# Sheet1.net
KiCad netlist of a schematic drawn in Altium Designer
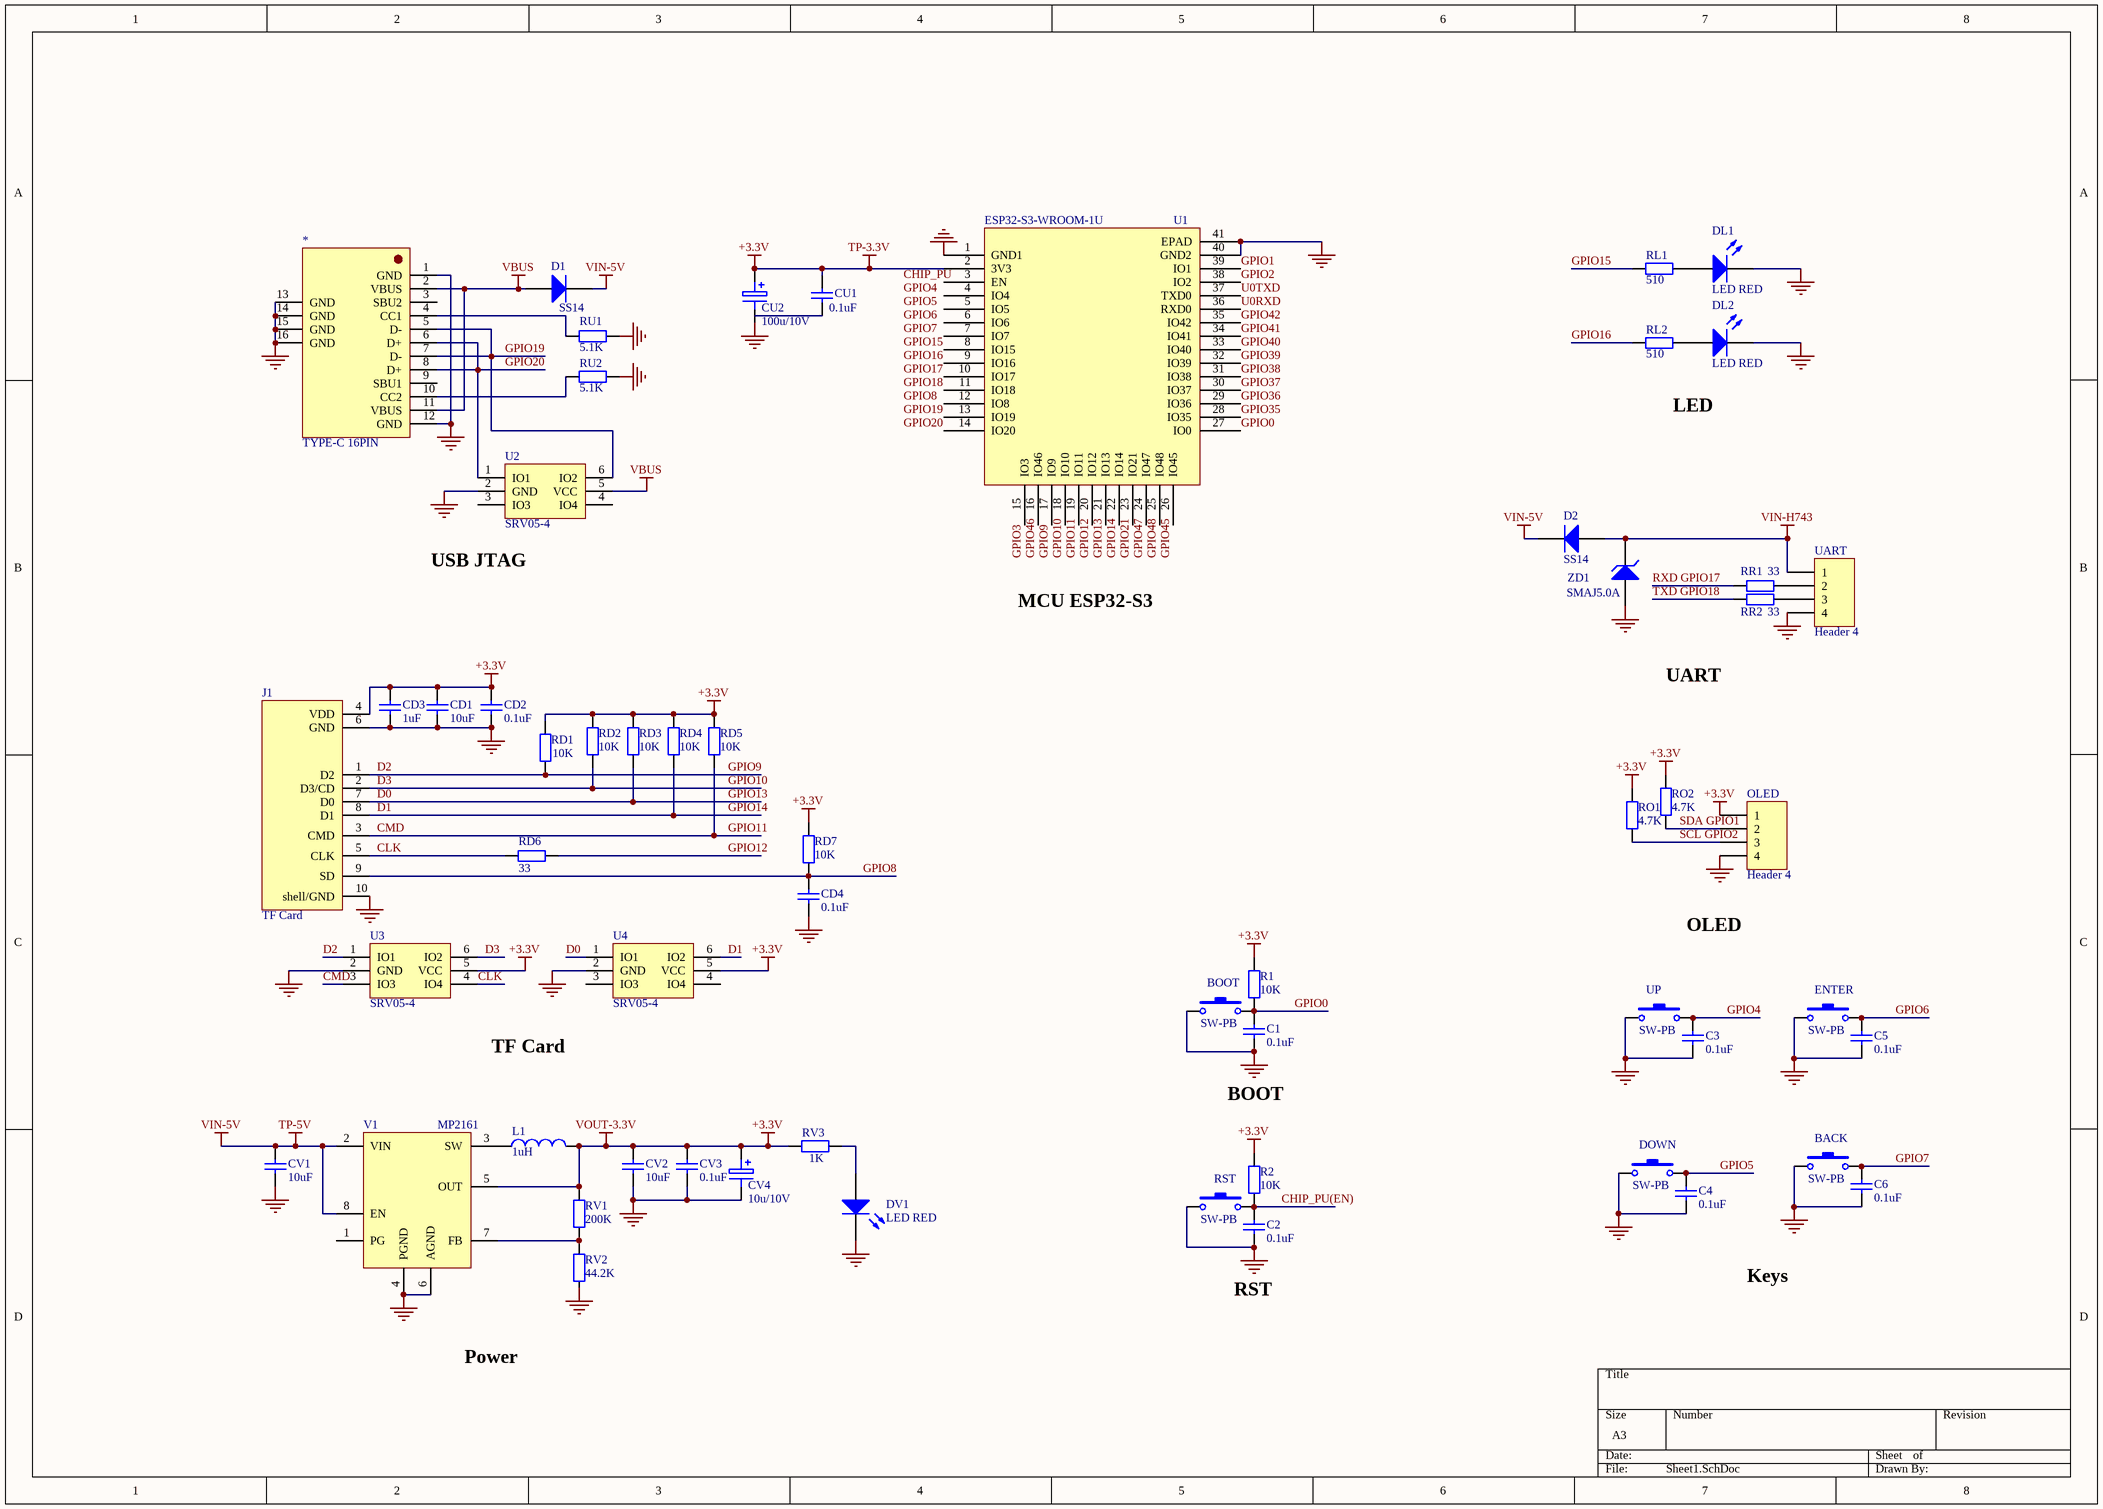
[diagram p0: Sheet1.SchDoc]

(export (version "E")
  (design (tool "Eeschema 10.0.6"))
  (components
    (comp (ref "*") (value "TYPE-C 16PIN") (libsource (lib "Schlib1") (part "TYPE-C 16PIN")))
    (comp (ref "BACK")
      (value "SW-PB")
      (footprint "SPST-2")
      (description "Switch")
      (fields (field (name "PUBLISHER") "Altium Limited"))
      (libsource (lib "Miscellaneous Devices") (part "SW-PB"))
    )
    (comp (ref "BOOT")
      (value "SW-PB")
      (footprint "SPST-2")
      (description "Switch")
      (fields (field (name "PUBLISHER") "Altium Limited"))
      (libsource (lib "Miscellaneous Devices") (part "SW-PB"))
    )
    (comp (ref "C1")
      (value "0.1uF")
      (footprint "RAD-0.3")
      (description "Capacitor")
      (fields (field (name "Comment") "Cap") (field (name "PUBLISHER") "Altium Limited"))
      (libsource (lib "Miscellaneous Devices") (part "Cap"))
    )
    (comp (ref "C2")
      (value "0.1uF")
      (footprint "RAD-0.3")
      (description "Capacitor")
      (fields (field (name "Comment") "Cap") (field (name "PUBLISHER") "Altium Limited"))
      (libsource (lib "Miscellaneous Devices") (part "Cap"))
    )
    (comp (ref "C3")
      (value "0.1uF")
      (footprint "RAD-0.3")
      (description "Capacitor")
      (fields (field (name "Comment") "Cap") (field (name "PUBLISHER") "Altium Limited"))
      (libsource (lib "Miscellaneous Devices") (part "Cap"))
    )
    (comp (ref "C4")
      (value "0.1uF")
      (footprint "RAD-0.3")
      (description "Capacitor")
      (fields (field (name "Comment") "Cap") (field (name "PUBLISHER") "Altium Limited"))
      (libsource (lib "Miscellaneous Devices") (part "Cap"))
    )
    (comp (ref "C5")
      (value "0.1uF")
      (footprint "RAD-0.3")
      (description "Capacitor")
      (fields (field (name "Comment") "Cap") (field (name "PUBLISHER") "Altium Limited"))
      (libsource (lib "Miscellaneous Devices") (part "Cap"))
    )
    (comp (ref "C6")
      (value "0.1uF")
      (footprint "RAD-0.3")
      (description "Capacitor")
      (fields (field (name "Comment") "Cap") (field (name "PUBLISHER") "Altium Limited"))
      (libsource (lib "Miscellaneous Devices") (part "Cap"))
    )
    (comp (ref "CD1")
      (value "10uF")
      (footprint "RAD-0.3")
      (description "Capacitor")
      (fields (field (name "Comment") "Cap") (field (name "PUBLISHER") "Altium Limited"))
      (libsource (lib "Miscellaneous Devices") (part "Cap"))
    )
    (comp (ref "CD2")
      (value "0.1uF")
      (footprint "RAD-0.3")
      (description "Capacitor")
      (fields (field (name "Comment") "Cap") (field (name "PUBLISHER") "Altium Limited"))
      (libsource (lib "Miscellaneous Devices") (part "Cap"))
    )
    (comp (ref "CD3")
      (value "1uF")
      (footprint "RAD-0.3")
      (description "Capacitor")
      (fields (field (name "Comment") "Cap") (field (name "PUBLISHER") "Altium Limited"))
      (libsource (lib "Miscellaneous Devices") (part "Cap"))
    )
    (comp (ref "CD4")
      (value "0.1uF")
      (footprint "RAD-0.3")
      (description "Capacitor")
      (fields (field (name "Comment") "Cap") (field (name "PUBLISHER") "Altium Limited"))
      (libsource (lib "Miscellaneous Devices") (part "Cap"))
    )
    (comp (ref "CU1")
      (value "0.1uF")
      (footprint "RAD-0.3")
      (description "Capacitor")
      (fields (field (name "Comment") "Cap") (field (name "PUBLISHER") "Altium Limited"))
      (libsource (lib "Miscellaneous Devices") (part "Cap"))
    )
    (comp (ref "CU2")
      (value "100u/10V")
      (description "Electrolytic Capacitor")
      (libsource (lib "*") (part "ELECTRO1"))
    )
    (comp (ref "CV1")
      (value "10uF")
      (footprint "RAD-0.3")
      (description "Capacitor")
      (fields (field (name "Comment") "Cap") (field (name "PUBLISHER") "Altium Limited"))
      (libsource (lib "Miscellaneous Devices") (part "Cap"))
    )
    (comp (ref "CV2")
      (value "10uF")
      (footprint "RAD-0.3")
      (description "Capacitor")
      (fields (field (name "Comment") "Cap") (field (name "PUBLISHER") "Altium Limited"))
      (libsource (lib "Miscellaneous Devices") (part "Cap"))
    )
    (comp (ref "CV3")
      (value "0.1uF")
      (footprint "RAD-0.3")
      (description "Capacitor")
      (fields (field (name "Comment") "Cap") (field (name "PUBLISHER") "Altium Limited"))
      (libsource (lib "Miscellaneous Devices") (part "Cap"))
    )
    (comp (ref "CV4")
      (value "10u/10V")
      (description "Electrolytic Capacitor")
      (libsource (lib "*") (part "ELECTRO1"))
    )
    (comp (ref "D1")
      (value "SS14")
      (footprint "SMC")
      (description "Default Diode")
      (fields (field (name "PUBLISHER") "Altium Limited"))
      (libsource (lib "Miscellaneous Devices") (part "Diode"))
    )
    (comp (ref "D2")
      (value "SS14")
      (footprint "SMC")
      (description "Default Diode")
      (fields (field (name "PUBLISHER") "Altium Limited"))
      (libsource (lib "Miscellaneous Devices") (part "Diode"))
    )
    (comp (ref "DL1")
      (value "LED RED")
      (footprint "3.2X1.6X1.1")
      (description "Typical RED, GREEN, YELLOW, AMBER GaAs LED")
      (fields (field (name "PUBLISHER") "Altium Limited"))
      (libsource (lib "Miscellaneous Devices") (part "LED2"))
    )
    (comp (ref "DL2")
      (value "LED RED")
      (footprint "3.2X1.6X1.1")
      (description "Typical RED, GREEN, YELLOW, AMBER GaAs LED")
      (fields (field (name "PUBLISHER") "Altium Limited"))
      (libsource (lib "Miscellaneous Devices") (part "LED2"))
    )
    (comp (ref "DOWN")
      (value "SW-PB")
      (footprint "SPST-2")
      (description "Switch")
      (fields (field (name "PUBLISHER") "Altium Limited"))
      (libsource (lib "Miscellaneous Devices") (part "SW-PB"))
    )
    (comp (ref "DV1")
      (value "LED RED")
      (footprint "3.2X1.6X1.1")
      (description "Typical RED, GREEN, YELLOW, AMBER GaAs LED")
      (fields (field (name "PUBLISHER") "Altium Limited"))
      (libsource (lib "Miscellaneous Devices") (part "LED2"))
    )
    (comp (ref "ENTER")
      (value "SW-PB")
      (footprint "SPST-2")
      (description "Switch")
      (fields (field (name "PUBLISHER") "Altium Limited"))
      (libsource (lib "Miscellaneous Devices") (part "SW-PB"))
    )
    (comp (ref "ESP32-S3-WROOM-1U") (value "U1") (libsource (lib "Schlib1") (part "ESP32-S3-WROOM-1U")))
    (comp (ref "J1") (value "TF Card") (libsource (lib "Schlib1") (part "TF Card")))
    (comp (ref "L1")
      (value "1uH")
      (footprint "0402-A")
      (description "Inductor")
      (fields (field (name "PUBLISHER") "Altium Limited"))
      (libsource (lib "Miscellaneous Devices") (part "Inductor"))
    )
    (comp (ref "OLED")
      (value "Header 4")
      (footprint "HDR1X4")
      (description "Header, 4-Pin")
      (fields (field (name "PUBLISHER") "Altium Limited"))
      (libsource (lib "Miscellaneous Connectors") (part "Header 4"))
    )
    (comp (ref "R1")
      (value "10K")
      (footprint "AXIAL-0.4")
      (description "Resistor")
      (fields (field (name "Comment") "Res2") (field (name "PUBLISHER") "Altium Limited"))
      (libsource (lib "Miscellaneous Devices") (part "Res2"))
    )
    (comp (ref "R2")
      (value "10K")
      (footprint "AXIAL-0.4")
      (description "Resistor")
      (fields (field (name "Comment") "Res2") (field (name "PUBLISHER") "Altium Limited"))
      (libsource (lib "Miscellaneous Devices") (part "Res2"))
    )
    (comp (ref "RD1")
      (value "10K")
      (footprint "AXIAL-0.4")
      (description "Resistor")
      (fields (field (name "Comment") "Res2") (field (name "PUBLISHER") "Altium Limited"))
      (libsource (lib "Miscellaneous Devices") (part "Res2"))
    )
    (comp (ref "RD2")
      (value "10K")
      (footprint "AXIAL-0.4")
      (description "Resistor")
      (fields (field (name "Comment") "Res2") (field (name "PUBLISHER") "Altium Limited"))
      (libsource (lib "Miscellaneous Devices") (part "Res2"))
    )
    (comp (ref "RD3")
      (value "10K")
      (footprint "AXIAL-0.4")
      (description "Resistor")
      (fields (field (name "Comment") "Res2") (field (name "PUBLISHER") "Altium Limited"))
      (libsource (lib "Miscellaneous Devices") (part "Res2"))
    )
    (comp (ref "RD4")
      (value "10K")
      (footprint "AXIAL-0.4")
      (description "Resistor")
      (fields (field (name "Comment") "Res2") (field (name "PUBLISHER") "Altium Limited"))
      (libsource (lib "Miscellaneous Devices") (part "Res2"))
    )
    (comp (ref "RD5")
      (value "10K")
      (footprint "AXIAL-0.4")
      (description "Resistor")
      (fields (field (name "Comment") "Res2") (field (name "PUBLISHER") "Altium Limited"))
      (libsource (lib "Miscellaneous Devices") (part "Res2"))
    )
    (comp (ref "RD6")
      (value "33")
      (footprint "AXIAL-0.4")
      (description "Resistor")
      (fields (field (name "Comment") "Res2") (field (name "PUBLISHER") "Altium Limited"))
      (libsource (lib "") (part "Res2_1"))
    )
    (comp (ref "RD7")
      (value "10K")
      (footprint "AXIAL-0.4")
      (description "Resistor")
      (fields (field (name "Comment") "Res2") (field (name "PUBLISHER") "Altium Limited"))
      (libsource (lib "Miscellaneous Devices") (part "Res2"))
    )
    (comp (ref "RL1")
      (value "510")
      (footprint "AXIAL-0.4")
      (description "Resistor")
      (fields (field (name "PUBLISHER") "Altium Limited"))
      (libsource (lib "") (part "Res2_1"))
    )
    (comp (ref "RL2")
      (value "510")
      (footprint "AXIAL-0.4")
      (description "Resistor")
      (fields (field (name "PUBLISHER") "Altium Limited"))
      (libsource (lib "") (part "Res2_1"))
    )
    (comp (ref "RO1")
      (value "4.7K")
      (footprint "AXIAL-0.4")
      (description "Resistor")
      (fields (field (name "Comment") "Res2") (field (name "PUBLISHER") "Altium Limited"))
      (libsource (lib "Miscellaneous Devices") (part "Res2"))
    )
    (comp (ref "RO2")
      (value "4.7K")
      (footprint "AXIAL-0.4")
      (description "Resistor")
      (fields (field (name "Comment") "Res2") (field (name "PUBLISHER") "Altium Limited"))
      (libsource (lib "Miscellaneous Devices") (part "Res2"))
    )
    (comp (ref "RR1")
      (value "33")
      (footprint "AXIAL-0.4")
      (description "Resistor")
      (fields (field (name "Comment") "Res2") (field (name "PUBLISHER") "Altium Limited"))
      (libsource (lib "") (part "Res2_1"))
    )
    (comp (ref "RR2")
      (value "33")
      (footprint "AXIAL-0.4")
      (description "Resistor")
      (fields (field (name "Comment") "Res2") (field (name "PUBLISHER") "Altium Limited"))
      (libsource (lib "") (part "Res2_1"))
    )
    (comp (ref "RST")
      (value "SW-PB")
      (footprint "SPST-2")
      (description "Switch")
      (fields (field (name "PUBLISHER") "Altium Limited"))
      (libsource (lib "Miscellaneous Devices") (part "SW-PB"))
    )
    (comp (ref "RU1")
      (value "5.1K")
      (footprint "AXIAL-0.4")
      (description "Resistor")
      (fields (field (name "PUBLISHER") "Altium Limited"))
      (libsource (lib "") (part "Res2_1"))
    )
    (comp (ref "RU2")
      (value "5.1K")
      (footprint "AXIAL-0.4")
      (description "Resistor")
      (fields (field (name "PUBLISHER") "Altium Limited"))
      (libsource (lib "") (part "Res2_1"))
    )
    (comp (ref "RV1")
      (value "200K")
      (footprint "AXIAL-0.4")
      (description "Resistor")
      (fields (field (name "Comment") "Res2") (field (name "PUBLISHER") "Altium Limited"))
      (libsource (lib "Miscellaneous Devices") (part "Res2"))
    )
    (comp (ref "RV2")
      (value "44.2K")
      (footprint "AXIAL-0.4")
      (description "Resistor")
      (fields (field (name "Comment") "Res2") (field (name "PUBLISHER") "Altium Limited"))
      (libsource (lib "Miscellaneous Devices") (part "Res2"))
    )
    (comp (ref "RV3")
      (value "1K")
      (footprint "AXIAL-0.4")
      (description "Resistor")
      (fields (field (name "PUBLISHER") "Altium Limited"))
      (libsource (lib "") (part "Res2_1"))
    )
    (comp (ref "U2") (value "SRV05-4") (libsource (lib "Schlib1") (part "SRV05-4")))
    (comp (ref "U3") (value "SRV05-4") (libsource (lib "Schlib1") (part "SRV05-4")))
    (comp (ref "U4") (value "SRV05-4") (libsource (lib "Schlib1") (part "SRV05-4")))
    (comp (ref "UART")
      (value "Header 4")
      (footprint "HDR1X4")
      (description "Header, 4-Pin")
      (fields (field (name "PUBLISHER") "Altium Limited"))
      (libsource (lib "Miscellaneous Connectors") (part "Header 4"))
    )
    (comp (ref "UP")
      (value "SW-PB")
      (footprint "SPST-2")
      (description "Switch")
      (fields (field (name "PUBLISHER") "Altium Limited"))
      (libsource (lib "Miscellaneous Devices") (part "SW-PB"))
    )
    (comp (ref "V1") (value "MP2161") (libsource (lib "Schlib1") (part "MP2161")))
    (comp (ref "ZD1")
      (value "SMAJ5.0A")
      (footprint "DIODE-0.7")
      (description "Zener Diode")
      (fields (field (name "PUBLISHER") "Altium Limited"))
      (libsource (lib "Miscellaneous Devices") (part "D Zener"))
    )
  )
  (nets
    (net (code "1") (name "+3.3V") (class "Default")
      (node (ref "CD1") (pin "2") (pinfunction "2_2") (pintype "passive"))
      (node (ref "CD2") (pin "2") (pinfunction "2_2") (pintype "passive"))
      (node (ref "CD3") (pin "2") (pinfunction "2_2") (pintype "passive"))
      (node (ref "CU1") (pin "2") (pinfunction "2_2") (pintype "passive"))
      (node (ref "CU2") (pin "1") (pinfunction "1_1") (pintype "passive"))
      (node (ref "CV2") (pin "2") (pinfunction "2_2") (pintype "passive"))
      (node (ref "CV3") (pin "2") (pinfunction "2_2") (pintype "passive"))
      (node (ref "CV4") (pin "1") (pinfunction "1_1") (pintype "passive"))
      (node (ref "ESP32-S3-WROOM-1U") (pin "2") (pinfunction "3V3_2") (pintype "passive"))
      (node (ref "J1") (pin "4") (pinfunction "VDD_4") (pintype "passive"))
      (node (ref "L1") (pin "2") (pinfunction "2_2") (pintype "passive"))
      (node (ref "OLED") (pin "1") (pinfunction "1_1") (pintype "passive"))
      (node (ref "R1") (pin "2") (pinfunction "2_2") (pintype "passive"))
      (node (ref "R2") (pin "2") (pinfunction "2_2") (pintype "passive"))
      (node (ref "RD1") (pin "2") (pinfunction "2_2") (pintype "passive"))
      (node (ref "RD2") (pin "2") (pinfunction "2_2") (pintype "passive"))
      (node (ref "RD3") (pin "2") (pinfunction "2_2") (pintype "passive"))
      (node (ref "RD4") (pin "2") (pinfunction "2_2") (pintype "passive"))
      (node (ref "RD5") (pin "2") (pinfunction "2_2") (pintype "passive"))
      (node (ref "RD7") (pin "2") (pinfunction "2_2") (pintype "passive"))
      (node (ref "RO1") (pin "2") (pinfunction "2_2") (pintype "passive"))
      (node (ref "RO2") (pin "2") (pinfunction "2_2") (pintype "passive"))
      (node (ref "RV1") (pin "2") (pinfunction "2_2") (pintype "passive"))
      (node (ref "RV3") (pin "2") (pinfunction "2_2") (pintype "passive"))
      (node (ref "U3") (pin "5") (pinfunction "VCC_5") (pintype "passive"))
      (node (ref "U4") (pin "5") (pinfunction "VCC_5") (pintype "passive"))
      (node (ref "V1") (pin "5") (pinfunction "OUT_5") (pintype "passive"))
    )
    (net (code "3") (name "/CHIP_PU(EN)") (class "Default")
      (node (ref "C2") (pin "2") (pinfunction "2_2") (pintype "passive"))
      (node (ref "R2") (pin "1") (pinfunction "1_1") (pintype "passive"))
      (node (ref "RST") (pin "2") (pinfunction "2_2") (pintype "passive"))
    )
    (net (code "4") (name "/CLK") (class "Default")
      (node (ref "J1") (pin "5") (pinfunction "CLK_5") (pintype "passive"))
      (node (ref "RD6") (pin "2") (pinfunction "2_2") (pintype "passive"))
      (node (ref "U3") (pin "4") (pinfunction "IO4_4") (pintype "passive"))
    )
    (net (code "5") (name "/CMD") (class "Default")
      (node (ref "J1") (pin "3") (pinfunction "CMD_3") (pintype "passive"))
      (node (ref "RD5") (pin "1") (pinfunction "1_1") (pintype "passive"))
      (node (ref "U3") (pin "3") (pinfunction "IO3_3") (pintype "passive"))
    )
    (net (code "6") (name "/D0") (class "Default")
      (node (ref "J1") (pin "7") (pinfunction "D0_7") (pintype "passive"))
      (node (ref "RD3") (pin "1") (pinfunction "1_1") (pintype "passive"))
      (node (ref "U4") (pin "1") (pinfunction "IO1_1") (pintype "passive"))
    )
    (net (code "7") (name "/D1") (class "Default")
      (node (ref "J1") (pin "8") (pinfunction "D1_8") (pintype "passive"))
      (node (ref "RD4") (pin "1") (pinfunction "1_1") (pintype "passive"))
      (node (ref "U4") (pin "6") (pinfunction "IO2_6") (pintype "passive"))
    )
    (net (code "8") (name "/D2") (class "Default")
      (node (ref "J1") (pin "1") (pinfunction "D2_1") (pintype "passive"))
      (node (ref "RD1") (pin "1") (pinfunction "1_1") (pintype "passive"))
      (node (ref "U3") (pin "1") (pinfunction "IO1_1") (pintype "passive"))
    )
    (net (code "9") (name "/D3") (class "Default")
      (node (ref "J1") (pin "2") (pinfunction "D3/CD_2") (pintype "passive"))
      (node (ref "RD2") (pin "1") (pinfunction "1_1") (pintype "passive"))
      (node (ref "U3") (pin "6") (pinfunction "IO2_6") (pintype "passive"))
    )
    (net (code "10") (name "/GPIO0") (class "Default")
      (node (ref "BOOT") (pin "2") (pinfunction "2_2") (pintype "passive"))
      (node (ref "C1") (pin "2") (pinfunction "2_2") (pintype "passive"))
      (node (ref "ESP32-S3-WROOM-1U") (pin "27") (pinfunction "IO0_27") (pintype "passive"))
      (node (ref "R1") (pin "1") (pinfunction "1_1") (pintype "passive"))
    )
    (net (code "11") (name "/GPIO1") (class "Default")
      (node (ref "ESP32-S3-WROOM-1U") (pin "39") (pinfunction "IO1_39") (pintype "passive"))
    )
    (net (code "12") (name "/GPIO2") (class "Default")
      (node (ref "ESP32-S3-WROOM-1U") (pin "38") (pinfunction "IO2_38") (pintype "passive"))
    )
    (net (code "14") (name "/GPIO4") (class "Default")
      (node (ref "C3") (pin "2") (pinfunction "2_2") (pintype "passive"))
      (node (ref "UP") (pin "2") (pinfunction "2_2") (pintype "passive"))
    )
    (net (code "15") (name "/GPIO5") (class "Default")
      (node (ref "C4") (pin "2") (pinfunction "2_2") (pintype "passive"))
      (node (ref "DOWN") (pin "2") (pinfunction "2_2") (pintype "passive"))
    )
    (net (code "16") (name "/GPIO6") (class "Default")
      (node (ref "C5") (pin "2") (pinfunction "2_2") (pintype "passive"))
      (node (ref "ENTER") (pin "2") (pinfunction "2_2") (pintype "passive"))
    )
    (net (code "17") (name "/GPIO7") (class "Default")
      (node (ref "BACK") (pin "2") (pinfunction "2_2") (pintype "passive"))
      (node (ref "C6") (pin "2") (pinfunction "2_2") (pintype "passive"))
    )
    (net (code "18") (name "/GPIO8") (class "Default")
      (node (ref "CD4") (pin "2") (pinfunction "2_2") (pintype "passive"))
      (node (ref "J1") (pin "9") (pinfunction "SD_9") (pintype "passive"))
      (node (ref "RD7") (pin "1") (pinfunction "1_1") (pintype "passive"))
    )
    (net (code "19") (name "/GPIO12") (class "Default")
      (node (ref "RD6") (pin "1") (pinfunction "1_1") (pintype "passive"))
    )
    (net (code "20") (name "/GPIO15") (class "Default")
      (node (ref "RL1") (pin "2") (pinfunction "2_2") (pintype "passive"))
    )
    (net (code "21") (name "/GPIO16") (class "Default")
      (node (ref "RL2") (pin "2") (pinfunction "2_2") (pintype "passive"))
    )
    (net (code "24") (name "/GPIO19") (class "Default")
      (node (ref "*") (pin "5") (pinfunction "D-_5") (pintype "passive"))
      (node (ref "*") (pin "7") (pinfunction "D-_7") (pintype "passive"))
      (node (ref "U2") (pin "6") (pinfunction "IO2_6") (pintype "passive"))
    )
    (net (code "25") (name "/GPIO20") (class "Default")
      (node (ref "*") (pin "6") (pinfunction "D+_6") (pintype "passive"))
      (node (ref "*") (pin "8") (pinfunction "D+_8") (pintype "passive"))
      (node (ref "U2") (pin "1") (pinfunction "IO1_1") (pintype "passive"))
    )
    (net (code "27") (name "/GPIO35") (class "Default")
      (node (ref "ESP32-S3-WROOM-1U") (pin "28") (pinfunction "IO35_28") (pintype "passive"))
    )
    (net (code "28") (name "/GPIO36") (class "Default")
      (node (ref "ESP32-S3-WROOM-1U") (pin "29") (pinfunction "IO36_29") (pintype "passive"))
    )
    (net (code "29") (name "/GPIO37") (class "Default")
      (node (ref "ESP32-S3-WROOM-1U") (pin "30") (pinfunction "IO37_30") (pintype "passive"))
    )
    (net (code "30") (name "/GPIO38") (class "Default")
      (node (ref "ESP32-S3-WROOM-1U") (pin "31") (pinfunction "IO38_31") (pintype "passive"))
    )
    (net (code "31") (name "/GPIO39") (class "Default")
      (node (ref "ESP32-S3-WROOM-1U") (pin "32") (pinfunction "IO39_32") (pintype "passive"))
    )
    (net (code "32") (name "/GPIO40") (class "Default")
      (node (ref "ESP32-S3-WROOM-1U") (pin "33") (pinfunction "IO40_33") (pintype "passive"))
    )
    (net (code "33") (name "/GPIO41") (class "Default")
      (node (ref "ESP32-S3-WROOM-1U") (pin "34") (pinfunction "IO41_34") (pintype "passive"))
    )
    (net (code "34") (name "/GPIO42") (class "Default")
      (node (ref "ESP32-S3-WROOM-1U") (pin "35") (pinfunction "IO42_35") (pintype "passive"))
    )
    (net (code "39") (name "/RXD GPIO17") (class "Default")
      (node (ref "RR1") (pin "2") (pinfunction "2_2") (pintype "passive"))
    )
    (net (code "40") (name "/SCL GPIO2") (class "Default")
      (node (ref "OLED") (pin "3") (pinfunction "3_3") (pintype "passive"))
      (node (ref "RO1") (pin "1") (pinfunction "1_1") (pintype "passive"))
    )
    (net (code "41") (name "/SDA GPIO1") (class "Default")
      (node (ref "OLED") (pin "2") (pinfunction "2_2") (pintype "passive"))
      (node (ref "RO2") (pin "1") (pinfunction "1_1") (pintype "passive"))
    )
    (net (code "42") (name "/TXD GPIO18") (class "Default")
      (node (ref "RR2") (pin "2") (pinfunction "2_2") (pintype "passive"))
    )
    (net (code "43") (name "/U0RXD") (class "Default")
      (node (ref "ESP32-S3-WROOM-1U") (pin "36") (pinfunction "RXD0_36") (pintype "passive"))
    )
    (net (code "44") (name "/U0TXD") (class "Default")
      (node (ref "ESP32-S3-WROOM-1U") (pin "37") (pinfunction "TXD0_37") (pintype "passive"))
    )
    (net (code "45") (name "GND") (class "Default")
      (node (ref "*") (pin "1") (pinfunction "GND_1") (pintype "passive"))
      (node (ref "*") (pin "12") (pinfunction "GND_12") (pintype "passive"))
      (node (ref "*") (pin "13") (pinfunction "GND_13") (pintype "passive"))
      (node (ref "*") (pin "14") (pinfunction "GND_14") (pintype "passive"))
      (node (ref "*") (pin "15") (pinfunction "GND_15") (pintype "passive"))
      (node (ref "*") (pin "16") (pinfunction "GND_16") (pintype "passive"))
      (node (ref "BACK") (pin "1") (pinfunction "1_1") (pintype "passive"))
      (node (ref "BOOT") (pin "1") (pinfunction "1_1") (pintype "passive"))
      (node (ref "C1") (pin "1") (pinfunction "1_1") (pintype "passive"))
      (node (ref "C2") (pin "1") (pinfunction "1_1") (pintype "passive"))
      (node (ref "C3") (pin "1") (pinfunction "1_1") (pintype "passive"))
      (node (ref "C4") (pin "1") (pinfunction "1_1") (pintype "passive"))
      (node (ref "C5") (pin "1") (pinfunction "1_1") (pintype "passive"))
      (node (ref "C6") (pin "1") (pinfunction "1_1") (pintype "passive"))
      (node (ref "CD1") (pin "1") (pinfunction "1_1") (pintype "passive"))
      (node (ref "CD2") (pin "1") (pinfunction "1_1") (pintype "passive"))
      (node (ref "CD3") (pin "1") (pinfunction "1_1") (pintype "passive"))
      (node (ref "CD4") (pin "1") (pinfunction "1_1") (pintype "passive"))
      (node (ref "CU2") (pin "2") (pinfunction "2_2") (pintype "passive"))
      (node (ref "CV1") (pin "1") (pinfunction "1_1") (pintype "passive"))
      (node (ref "CV2") (pin "1") (pinfunction "1_1") (pintype "passive"))
      (node (ref "CV3") (pin "1") (pinfunction "1_1") (pintype "passive"))
      (node (ref "CV4") (pin "2") (pinfunction "2_2") (pintype "passive"))
      (node (ref "DL1") (pin "2") (pinfunction "K_2") (pintype "passive"))
      (node (ref "DL2") (pin "2") (pinfunction "K_2") (pintype "passive"))
      (node (ref "DOWN") (pin "1") (pinfunction "1_1") (pintype "passive"))
      (node (ref "DV1") (pin "2") (pinfunction "K_2") (pintype "passive"))
      (node (ref "ENTER") (pin "1") (pinfunction "1_1") (pintype "passive"))
      (node (ref "ESP32-S3-WROOM-1U") (pin "1") (pinfunction "GND1_1") (pintype "passive"))
      (node (ref "ESP32-S3-WROOM-1U") (pin "40") (pinfunction "GND2_40") (pintype "passive"))
      (node (ref "ESP32-S3-WROOM-1U") (pin "41") (pinfunction "EPAD_41") (pintype "passive"))
      (node (ref "J1") (pin "10") (pinfunction "shell/GND_10") (pintype "passive"))
      (node (ref "J1") (pin "6") (pinfunction "GND_6") (pintype "passive"))
      (node (ref "OLED") (pin "4") (pinfunction "4_4") (pintype "passive"))
      (node (ref "RST") (pin "1") (pinfunction "1_1") (pintype "passive"))
      (node (ref "RU1") (pin "1") (pinfunction "1_1") (pintype "passive"))
      (node (ref "RU2") (pin "1") (pinfunction "1_1") (pintype "passive"))
      (node (ref "U2") (pin "2") (pinfunction "GND_2") (pintype "passive"))
      (node (ref "U3") (pin "2") (pinfunction "GND_2") (pintype "passive"))
      (node (ref "U4") (pin "2") (pinfunction "GND_2") (pintype "passive"))
      (node (ref "UART") (pin "4") (pinfunction "4_4") (pintype "passive"))
      (node (ref "UP") (pin "1") (pinfunction "1_1") (pintype "passive"))
      (node (ref "V1") (pin "4") (pinfunction "PGND_4") (pintype "passive"))
      (node (ref "V1") (pin "6") (pinfunction "AGND_6") (pintype "passive"))
      (node (ref "ZD1") (pin "1") (pinfunction "A_1") (pintype "passive"))
    )
    (net (code "46") (name "Net-(*-CC1)") (class "Default")
      (node (ref "*") (pin "4") (pinfunction "CC1_4") (pintype "passive"))
      (node (ref "RU1") (pin "2") (pinfunction "2_2") (pintype "passive"))
    )
    (net (code "47") (name "Net-(*-CC2)") (class "Default")
      (node (ref "*") (pin "10") (pinfunction "CC2_10") (pintype "passive"))
      (node (ref "RU2") (pin "2") (pinfunction "2_2") (pintype "passive"))
    )
    (net (code "48") (name "Net-(DL1-A)") (class "Default")
      (node (ref "DL1") (pin "1") (pinfunction "A_1") (pintype "passive"))
      (node (ref "RL1") (pin "1") (pinfunction "1_1") (pintype "passive"))
    )
    (net (code "49") (name "Net-(DL2-A)") (class "Default")
      (node (ref "DL2") (pin "1") (pinfunction "A_1") (pintype "passive"))
      (node (ref "RL2") (pin "1") (pinfunction "1_1") (pintype "passive"))
    )
    (net (code "50") (name "Net-(DV1-A)") (class "Default")
      (node (ref "DV1") (pin "1") (pinfunction "A_1") (pintype "passive"))
      (node (ref "RV3") (pin "1") (pinfunction "1_1") (pintype "passive"))
    )
    (net (code "51") (name "Net-(RR1-Pad1)") (class "Default")
      (node (ref "RR1") (pin "1") (pinfunction "1_1") (pintype "passive"))
      (node (ref "UART") (pin "2") (pinfunction "2_2") (pintype "passive"))
    )
    (net (code "52") (name "Net-(RR2-Pad1)") (class "Default")
      (node (ref "RR2") (pin "1") (pinfunction "1_1") (pintype "passive"))
      (node (ref "UART") (pin "3") (pinfunction "3_3") (pintype "passive"))
    )
    (net (code "53") (name "Net-(V1-FB)") (class "Default")
      (node (ref "RV1") (pin "1") (pinfunction "1_1") (pintype "passive"))
      (node (ref "RV2") (pin "2") (pinfunction "2_2") (pintype "passive"))
      (node (ref "V1") (pin "7") (pinfunction "FB_7") (pintype "passive"))
    )
    (net (code "54") (name "Net-(V1-SW)") (class "Default")
      (node (ref "L1") (pin "1") (pinfunction "1_1") (pintype "passive"))
      (node (ref "V1") (pin "3") (pinfunction "SW_3") (pintype "passive"))
    )
    (net (code "55") (name "TP-5V") (class "Default")
      (node (ref "CV1") (pin "2") (pinfunction "2_2") (pintype "passive"))
      (node (ref "D1") (pin "2") (pinfunction "K_2") (pintype "passive"))
      (node (ref "D2") (pin "2") (pinfunction "K_2") (pintype "passive"))
      (node (ref "V1") (pin "2") (pinfunction "VIN_2") (pintype "passive"))
      (node (ref "V1") (pin "8") (pinfunction "EN_8") (pintype "passive"))
    )
    (net (code "56") (name "VBUS") (class "Default")
      (node (ref "*") (pin "11") (pinfunction "VBUS_11") (pintype "passive"))
      (node (ref "*") (pin "2") (pinfunction "VBUS_2") (pintype "passive"))
      (node (ref "D1") (pin "1") (pinfunction "A_1") (pintype "passive"))
      (node (ref "U2") (pin "5") (pinfunction "VCC_5") (pintype "passive"))
    )
    (net (code "57") (name "VIN-H743") (class "Default")
      (node (ref "D2") (pin "1") (pinfunction "A_1") (pintype "passive"))
      (node (ref "UART") (pin "1") (pinfunction "1_1") (pintype "passive"))
      (node (ref "ZD1") (pin "2") (pinfunction "K_2") (pintype "passive"))
    )
    (net (code "58") (name "unconnected-(*-SBU1-Pad9)") (class "Default")
      (node (ref "*") (pin "9") (pinfunction "SBU1_9") (pintype "passive"))
    )
    (net (code "59") (name "unconnected-(*-SBU2-Pad3)") (class "Default")
      (node (ref "*") (pin "3") (pinfunction "SBU2_3") (pintype "passive"))
    )
    (net (code "60") (name "unconnected-(CU1-Pad1)") (class "Default")
      (node (ref "CU1") (pin "1") (pinfunction "1_1") (pintype "passive"))
    )
    (net (code "61") (name "unconnected-(ESP32-S3-WROOM-1U-EN-Pad3)") (class "Default")
      (node (ref "ESP32-S3-WROOM-1U") (pin "3") (pinfunction "EN_3") (pintype "passive"))
    )
    (net (code "62") (name "unconnected-(ESP32-S3-WROOM-1U-IO3-Pad15)") (class "Default")
      (node (ref "ESP32-S3-WROOM-1U") (pin "15") (pinfunction "IO3_15") (pintype "passive"))
    )
    (net (code "63") (name "unconnected-(ESP32-S3-WROOM-1U-IO4-Pad4)") (class "Default")
      (node (ref "ESP32-S3-WROOM-1U") (pin "4") (pinfunction "IO4_4") (pintype "passive"))
    )
    (net (code "64") (name "unconnected-(ESP32-S3-WROOM-1U-IO5-Pad5)") (class "Default")
      (node (ref "ESP32-S3-WROOM-1U") (pin "5") (pinfunction "IO5_5") (pintype "passive"))
    )
    (net (code "65") (name "unconnected-(ESP32-S3-WROOM-1U-IO6-Pad6)") (class "Default")
      (node (ref "ESP32-S3-WROOM-1U") (pin "6") (pinfunction "IO6_6") (pintype "passive"))
    )
    (net (code "66") (name "unconnected-(ESP32-S3-WROOM-1U-IO7-Pad7)") (class "Default")
      (node (ref "ESP32-S3-WROOM-1U") (pin "7") (pinfunction "IO7_7") (pintype "passive"))
    )
    (net (code "67") (name "unconnected-(ESP32-S3-WROOM-1U-IO8-Pad12)") (class "Default")
      (node (ref "ESP32-S3-WROOM-1U") (pin "12") (pinfunction "IO8_12") (pintype "passive"))
    )
    (net (code "68") (name "unconnected-(ESP32-S3-WROOM-1U-IO9-Pad17)") (class "Default")
      (node (ref "ESP32-S3-WROOM-1U") (pin "17") (pinfunction "IO9_17") (pintype "passive"))
    )
    (net (code "69") (name "unconnected-(ESP32-S3-WROOM-1U-IO10-Pad18)") (class "Default")
      (node (ref "ESP32-S3-WROOM-1U") (pin "18") (pinfunction "IO10_18") (pintype "passive"))
    )
    (net (code "70") (name "unconnected-(ESP32-S3-WROOM-1U-IO11-Pad19)") (class "Default")
      (node (ref "ESP32-S3-WROOM-1U") (pin "19") (pinfunction "IO11_19") (pintype "passive"))
    )
    (net (code "71") (name "unconnected-(ESP32-S3-WROOM-1U-IO12-Pad20)") (class "Default")
      (node (ref "ESP32-S3-WROOM-1U") (pin "20") (pinfunction "IO12_20") (pintype "passive"))
    )
    (net (code "72") (name "unconnected-(ESP32-S3-WROOM-1U-IO13-Pad21)") (class "Default")
      (node (ref "ESP32-S3-WROOM-1U") (pin "21") (pinfunction "IO13_21") (pintype "passive"))
    )
    (net (code "73") (name "unconnected-(ESP32-S3-WROOM-1U-IO14-Pad22)") (class "Default")
      (node (ref "ESP32-S3-WROOM-1U") (pin "22") (pinfunction "IO14_22") (pintype "passive"))
    )
    (net (code "74") (name "unconnected-(ESP32-S3-WROOM-1U-IO15-Pad8)") (class "Default")
      (node (ref "ESP32-S3-WROOM-1U") (pin "8") (pinfunction "IO15_8") (pintype "passive"))
    )
    (net (code "75") (name "unconnected-(ESP32-S3-WROOM-1U-IO16-Pad9)") (class "Default")
      (node (ref "ESP32-S3-WROOM-1U") (pin "9") (pinfunction "IO16_9") (pintype "passive"))
    )
    (net (code "76") (name "unconnected-(ESP32-S3-WROOM-1U-IO17-Pad10)") (class "Default")
      (node (ref "ESP32-S3-WROOM-1U") (pin "10") (pinfunction "IO17_10") (pintype "passive"))
    )
    (net (code "77") (name "unconnected-(ESP32-S3-WROOM-1U-IO18-Pad11)") (class "Default")
      (node (ref "ESP32-S3-WROOM-1U") (pin "11") (pinfunction "IO18_11") (pintype "passive"))
    )
    (net (code "78") (name "unconnected-(ESP32-S3-WROOM-1U-IO19-Pad13)") (class "Default")
      (node (ref "ESP32-S3-WROOM-1U") (pin "13") (pinfunction "IO19_13") (pintype "passive"))
    )
    (net (code "79") (name "unconnected-(ESP32-S3-WROOM-1U-IO20-Pad14)") (class "Default")
      (node (ref "ESP32-S3-WROOM-1U") (pin "14") (pinfunction "IO20_14") (pintype "passive"))
    )
    (net (code "80") (name "unconnected-(ESP32-S3-WROOM-1U-IO21-Pad23)") (class "Default")
      (node (ref "ESP32-S3-WROOM-1U") (pin "23") (pinfunction "IO21_23") (pintype "passive"))
    )
    (net (code "81") (name "unconnected-(ESP32-S3-WROOM-1U-IO45-Pad26)") (class "Default")
      (node (ref "ESP32-S3-WROOM-1U") (pin "26") (pinfunction "IO45_26") (pintype "passive"))
    )
    (net (code "82") (name "unconnected-(ESP32-S3-WROOM-1U-IO46-Pad16)") (class "Default")
      (node (ref "ESP32-S3-WROOM-1U") (pin "16") (pinfunction "IO46_16") (pintype "passive"))
    )
    (net (code "83") (name "unconnected-(ESP32-S3-WROOM-1U-IO47-Pad24)") (class "Default")
      (node (ref "ESP32-S3-WROOM-1U") (pin "24") (pinfunction "IO47_24") (pintype "passive"))
    )
    (net (code "84") (name "unconnected-(ESP32-S3-WROOM-1U-IO48-Pad25)") (class "Default")
      (node (ref "ESP32-S3-WROOM-1U") (pin "25") (pinfunction "IO48_25") (pintype "passive"))
    )
    (net (code "85") (name "unconnected-(RV2-Pad1)") (class "Default")
      (node (ref "RV2") (pin "1") (pinfunction "1_1") (pintype "passive"))
    )
    (net (code "86") (name "unconnected-(U2-IO3-Pad3)") (class "Default")
      (node (ref "U2") (pin "3") (pinfunction "IO3_3") (pintype "passive"))
    )
    (net (code "87") (name "unconnected-(U2-IO4-Pad4)") (class "Default")
      (node (ref "U2") (pin "4") (pinfunction "IO4_4") (pintype "passive"))
    )
    (net (code "88") (name "unconnected-(U4-IO3-Pad3)") (class "Default")
      (node (ref "U4") (pin "3") (pinfunction "IO3_3") (pintype "passive"))
    )
    (net (code "89") (name "unconnected-(U4-IO4-Pad4)") (class "Default")
      (node (ref "U4") (pin "4") (pinfunction "IO4_4") (pintype "passive"))
    )
    (net (code "90") (name "unconnected-(V1-PG-Pad1)") (class "Default")
      (node (ref "V1") (pin "1") (pinfunction "PG_1") (pintype "passive"))
    )
  )
)
